# Pletacka_board.net
KiCad netlist of a schematic drawn in EAGLE
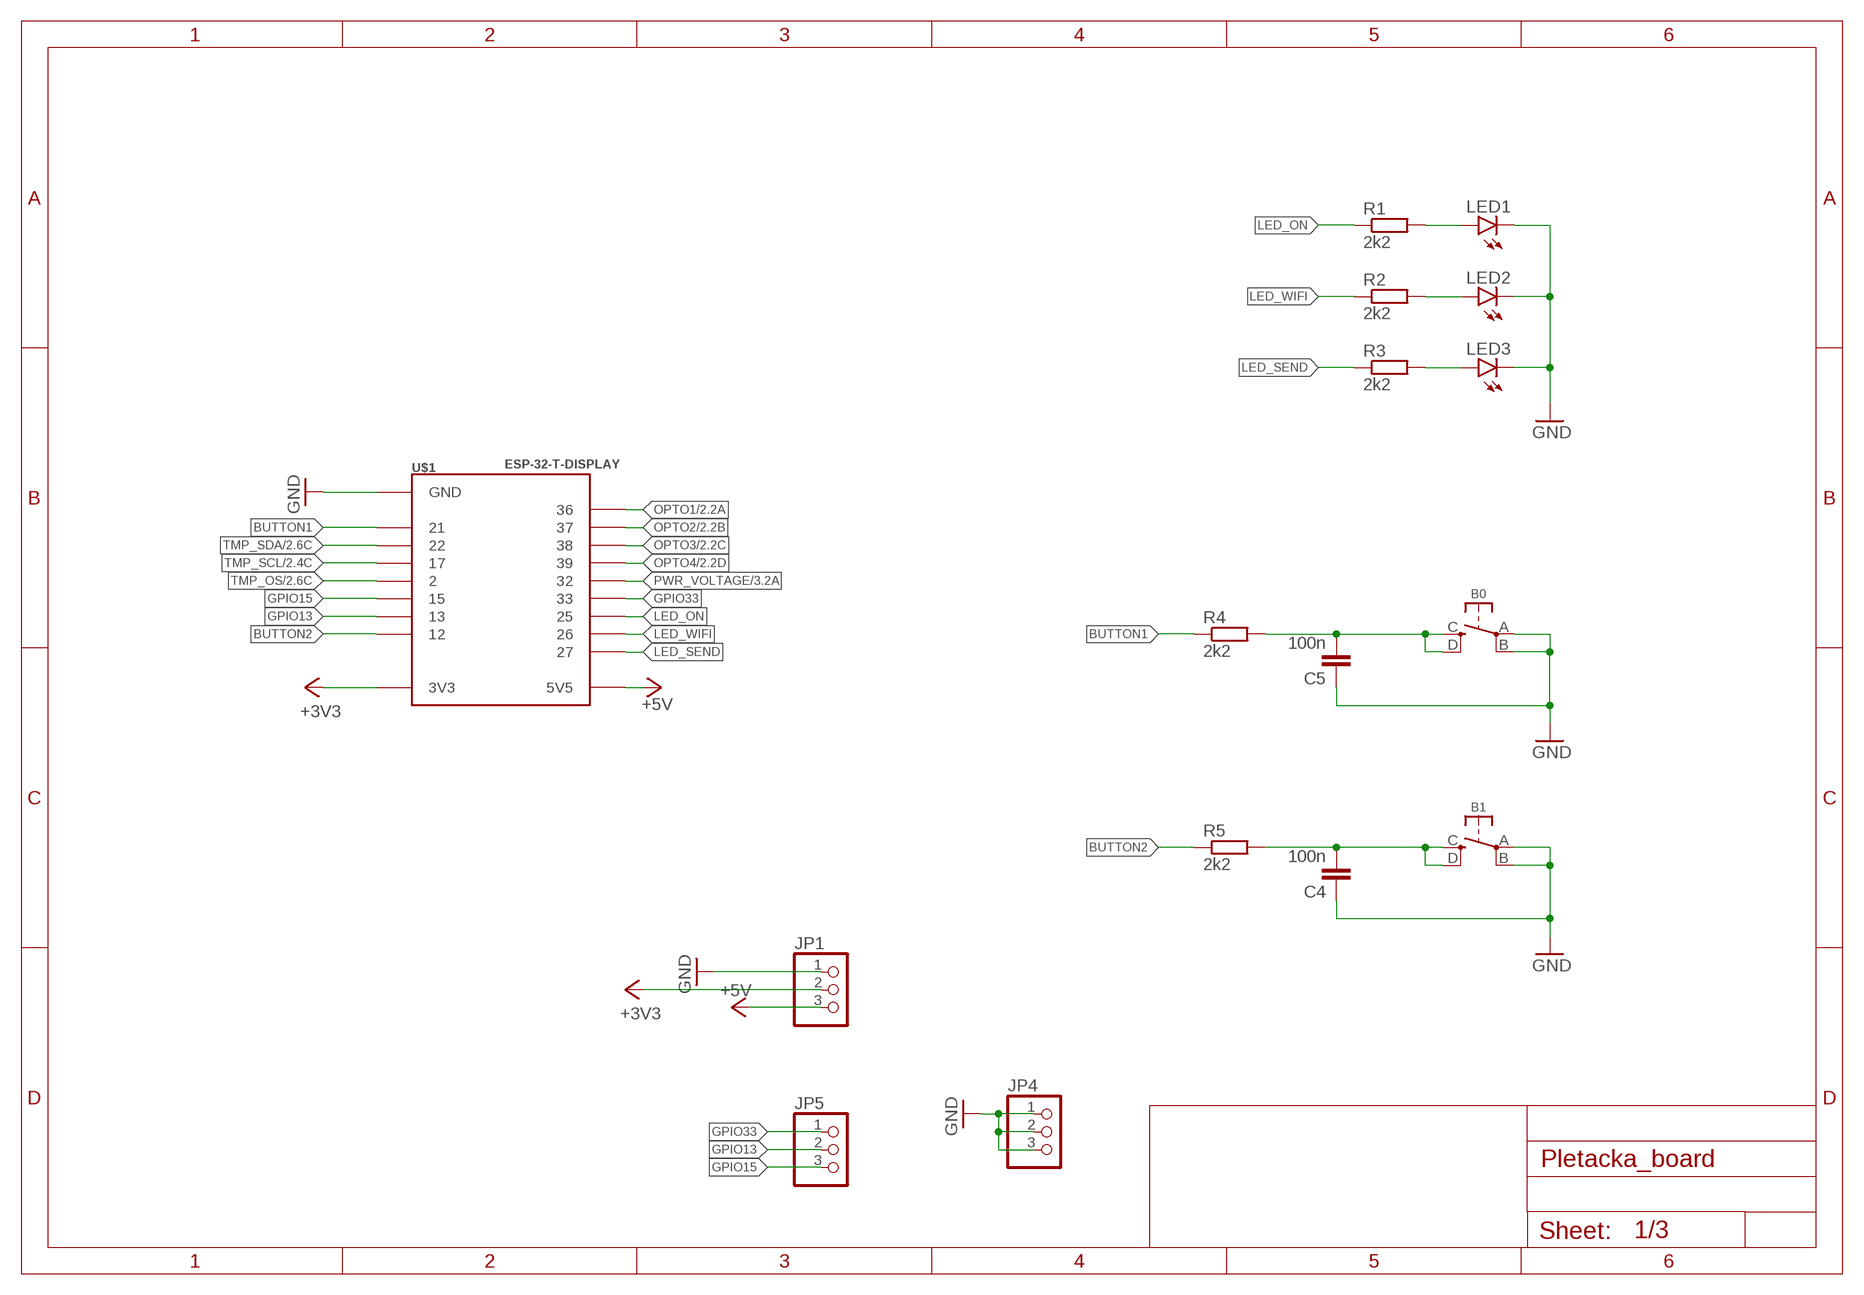
[diagram p0: schematic, sheet 1]
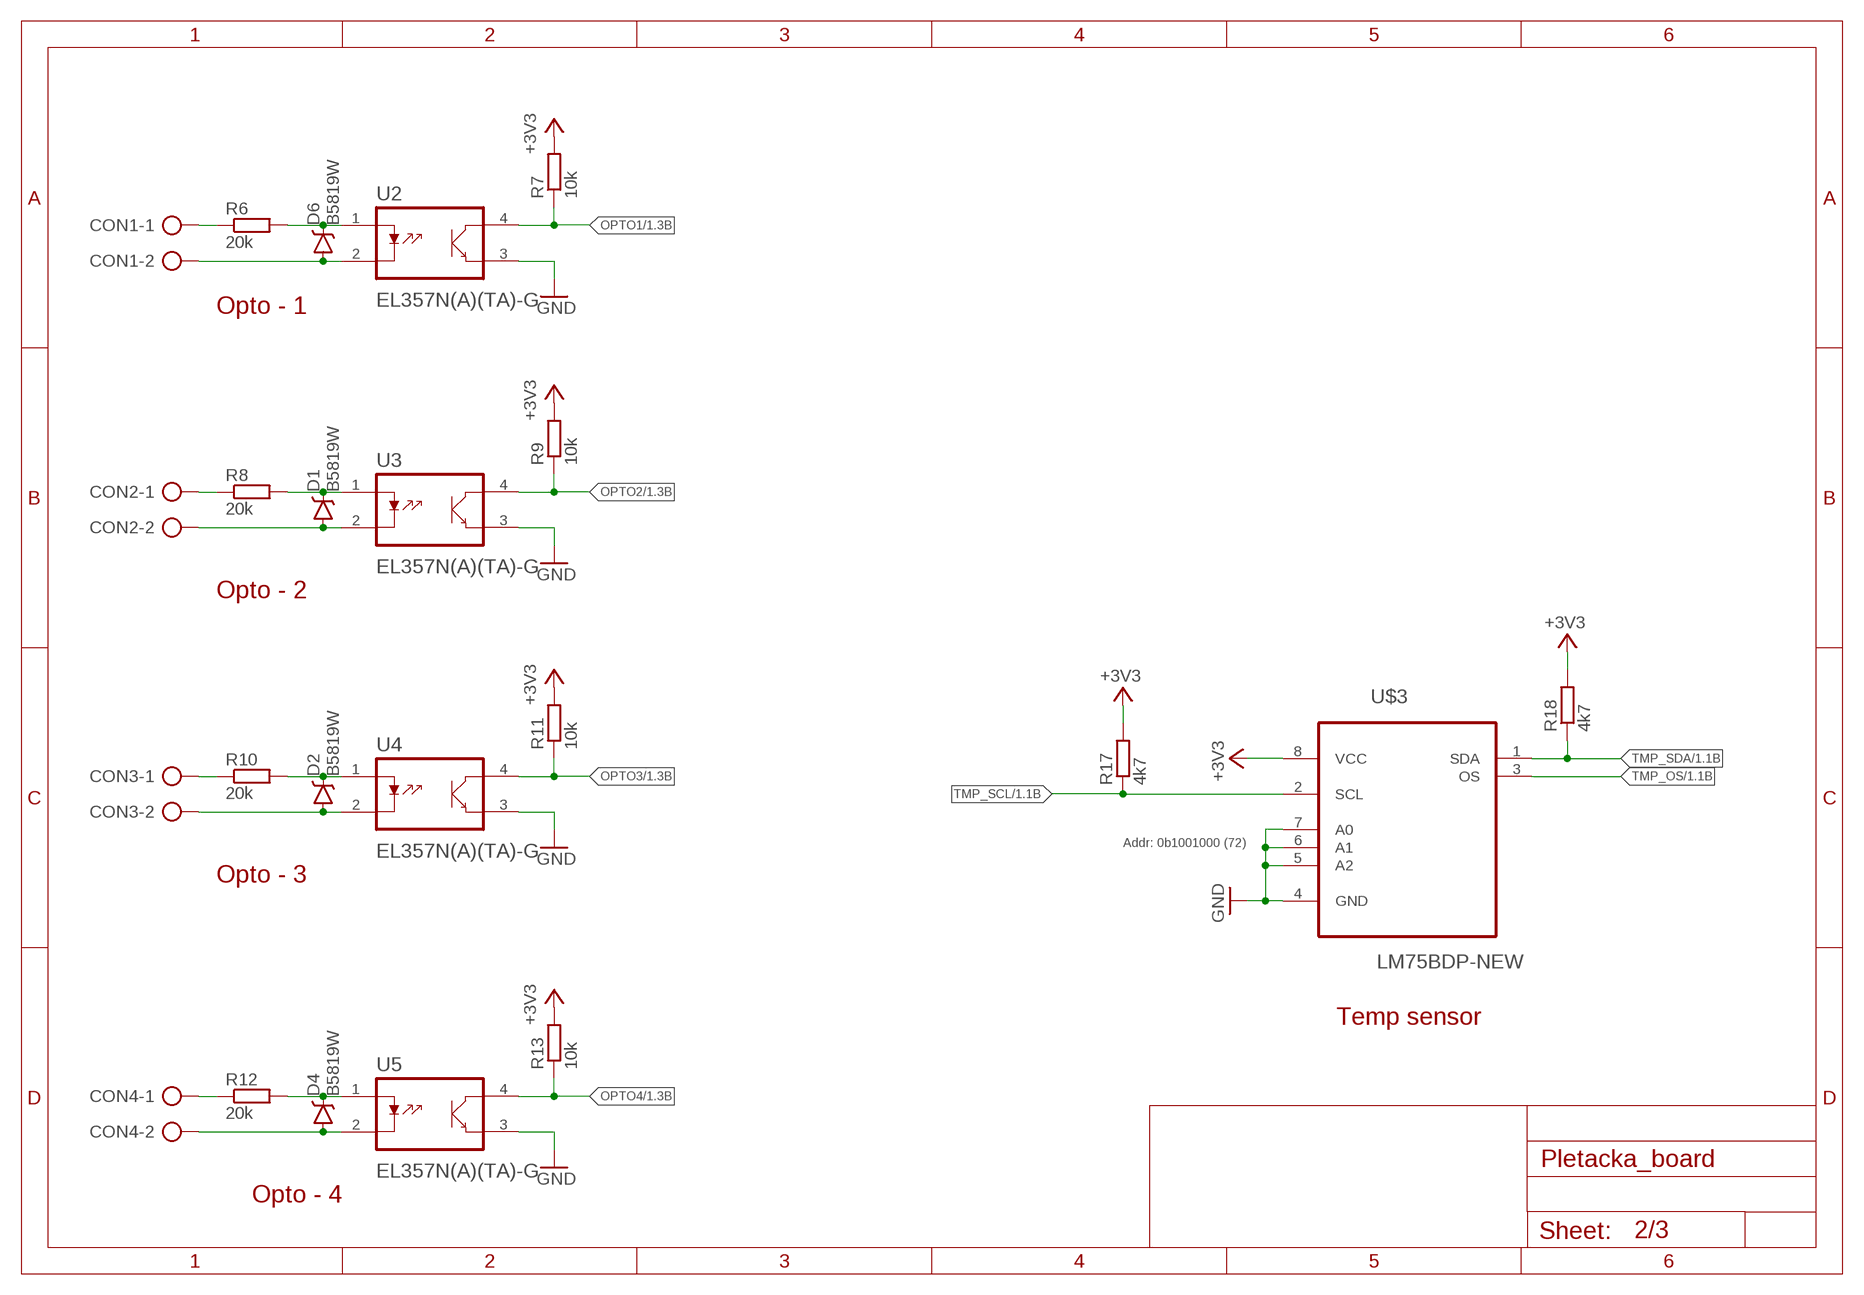
[diagram p1: schematic, sheet 2]
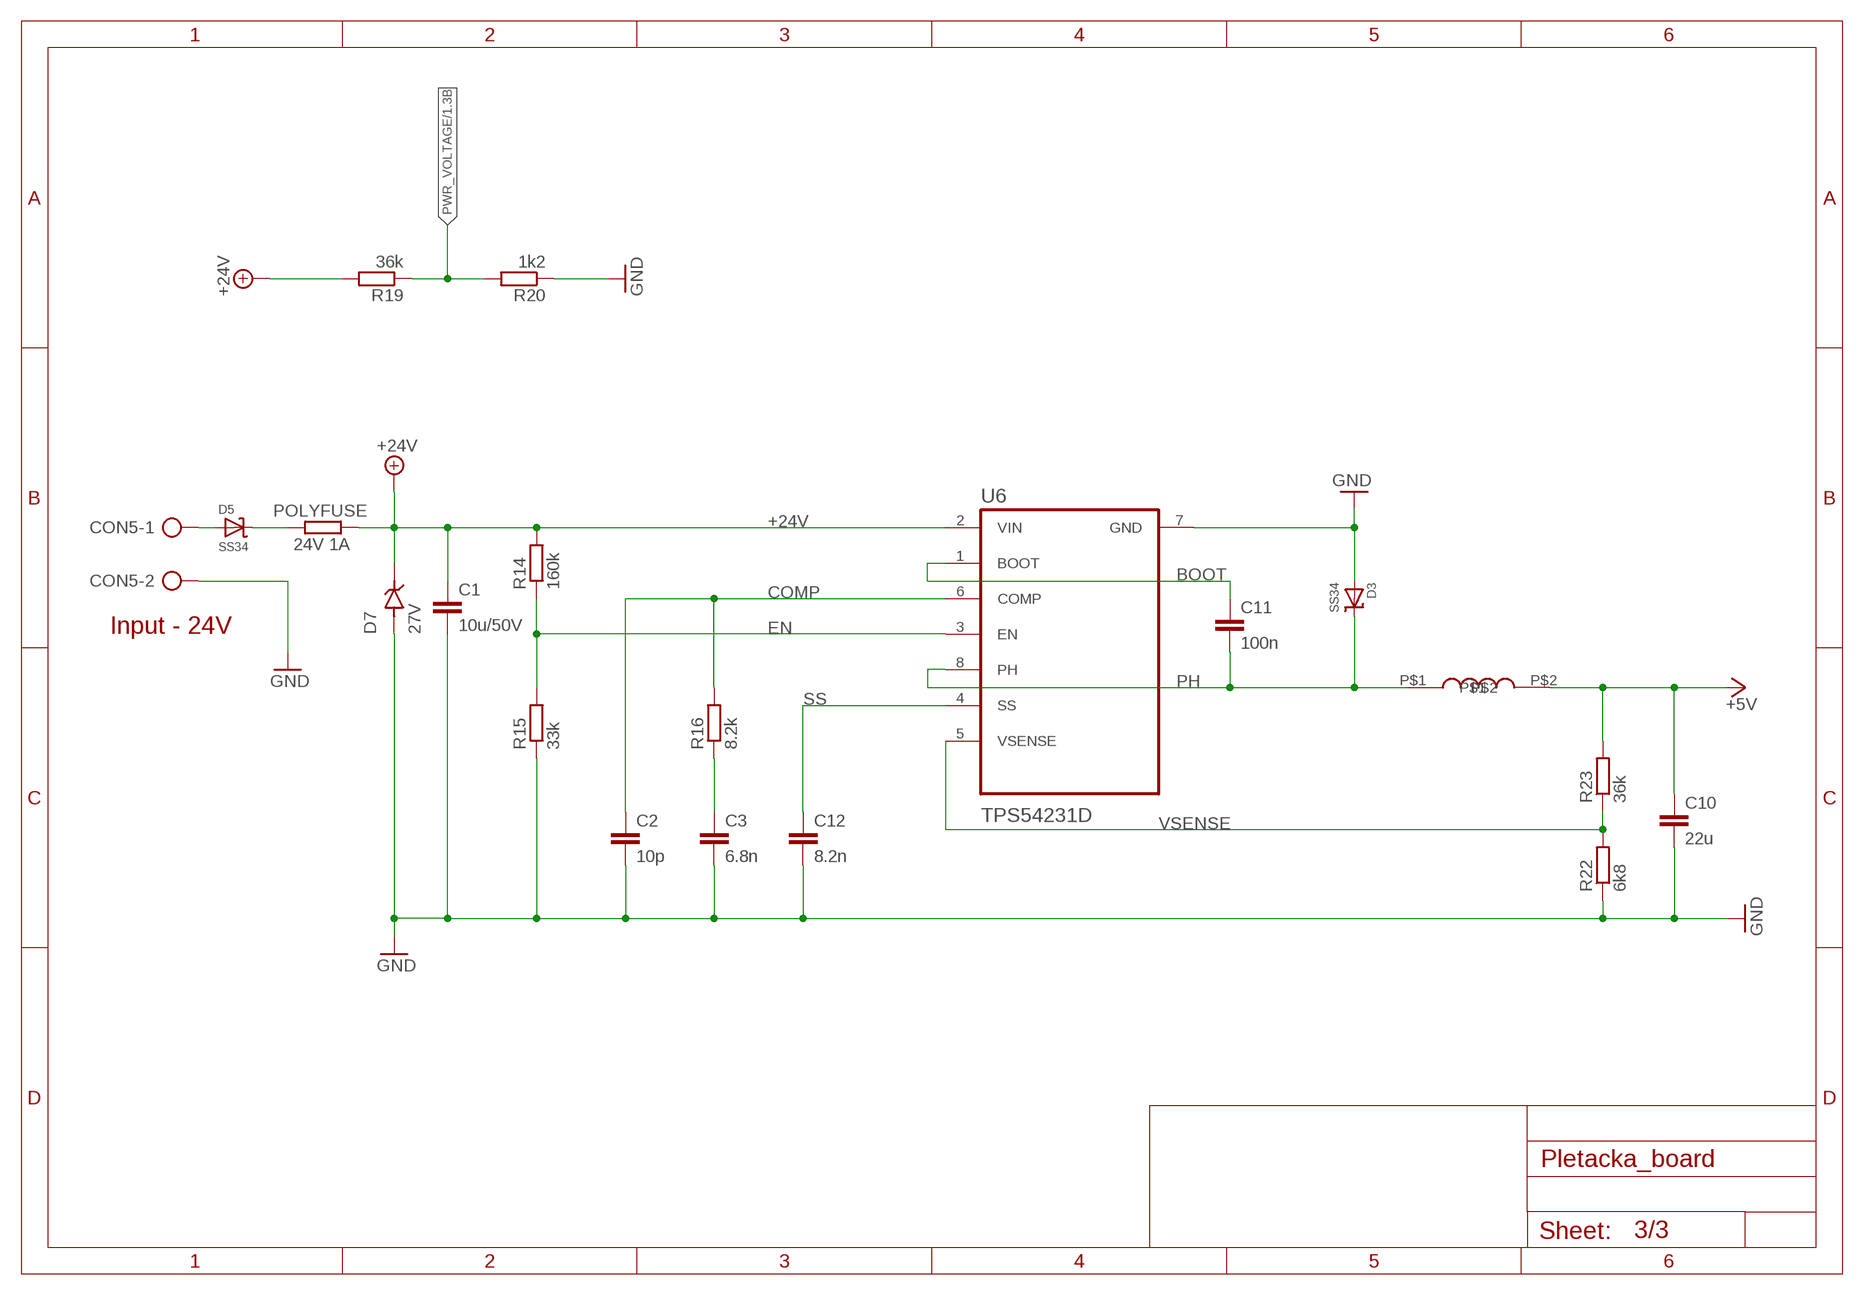
[diagram p2: schematic, sheet 3]

(export (version "E")
  (design (tool "Eeschema 10.0.6"))
  (components
    (comp (ref "C1")
      (value "10u/50V")
      (footprint "eagle-import:C1206")
      (libsource (lib "eagle-import") (part "C-EUC1206"))
    )
    (comp (ref "C2")
      (value "10p")
      (footprint "eagle-import:C0603")
      (libsource (lib "eagle-import") (part "C-EUC0603"))
    )
    (comp (ref "C3")
      (value "6.8n")
      (footprint "eagle-import:C0603")
      (libsource (lib "eagle-import") (part "C-EUC0603"))
    )
    (comp (ref "C10")
      (value "22u")
      (footprint "eagle-import:C0805")
      (libsource (lib "eagle-import") (part "C-EUC0805"))
    )
    (comp (ref "C11")
      (value "100n")
      (footprint "eagle-import:C0603")
      (libsource (lib "eagle-import") (part "C-EUC0603"))
    )
    (comp (ref "C12")
      (value "8.2n")
      (footprint "eagle-import:C0603")
      (libsource (lib "eagle-import") (part "C-EUC0603"))
    )
    (comp (ref "CON5")
      (value "AK500/2")
      (footprint "eagle-import:AK500_2")
      (libsource (lib "eagle-import") (part "AK500/2"))
    )
    (comp (ref "D3")
      (value "SS34")
      (footprint "eagle-import:SMA")
      (libsource (lib "eagle-import") (part "SHOTTKY-SMA"))
    )
    (comp (ref "D5")
      (value "SS34")
      (footprint "eagle-import:SMA")
      (libsource (lib "eagle-import") (part "SHOTTKY-SMA"))
    )
    (comp (ref "D7")
      (value "27V")
      (footprint "eagle-import:DIOM5436X247N")
      (fields (field (name "MF") "ON Semiconductor") (field (name "MP") "1SMB5935BT3G"))
      (libsource (lib "eagle-import") (part "1SMB5935BT3G"))
    )
    (comp (ref "POLYFUSE")
      (value "24V 1A")
      (footprint "eagle-import:R1206")
      (libsource (lib "eagle-import") (part "R-EU_R1206"))
    )
    (comp (ref "R14")
      (value "160k")
      (footprint "eagle-import:R0603")
      (libsource (lib "eagle-import") (part "R-EU_R0603"))
    )
    (comp (ref "R15")
      (value "33k")
      (footprint "eagle-import:R0603")
      (libsource (lib "eagle-import") (part "R-EU_R0603"))
    )
    (comp (ref "R16")
      (value "8.2k")
      (footprint "eagle-import:R0603")
      (libsource (lib "eagle-import") (part "R-EU_R0603"))
    )
    (comp (ref "R19")
      (value "36k")
      (footprint "eagle-import:R0603")
      (libsource (lib "eagle-import") (part "R-EU_R0603"))
    )
    (comp (ref "R20")
      (value "1k2")
      (footprint "eagle-import:R0603")
      (libsource (lib "eagle-import") (part "R-EU_R0603"))
    )
    (comp (ref "R22")
      (value "6k8")
      (footprint "eagle-import:R0603")
      (libsource (lib "eagle-import") (part "R-EU_R0603"))
    )
    (comp (ref "R23")
      (value "36k")
      (footprint "eagle-import:R0603")
      (libsource (lib "eagle-import") (part "R-EU_R0603"))
    )
    (comp (ref "U$2")
      (value "SWRB1204S")
      (footprint "eagle-import:SWRB1204S")
      (libsource (lib "eagle-import") (part "SWRB1204S"))
    )
    (comp (ref "U6")
      (value "TPS54231D")
      (footprint "eagle-import:SOIC127P599X175-8N")
      (description "3.5 to 28V Input, 2A, 570kHz Step-Down Converter with Eco-mode&trade, 8-SOIC -40 to 150")
      (fields (field (name "MF") "Texas Instruments"))
      (libsource (lib "eagle-import") (part "TPS54231D"))
    )
    (comp (ref "B0")
      (value "ENTER")
      (footprint "eagle-import:TS-1187A")
      (libsource (lib "eagle-import") (part "10-XX_SMD"))
    )
    (comp (ref "B1")
      (value "B1")
      (footprint "eagle-import:TS-1187A")
      (libsource (lib "eagle-import") (part "10-XX_SMD"))
    )
    (comp (ref "C4")
      (value "100n")
      (footprint "eagle-import:C0603")
      (libsource (lib "eagle-import") (part "C-EUC0603"))
    )
    (comp (ref "C5")
      (value "100n")
      (footprint "eagle-import:C0603")
      (libsource (lib "eagle-import") (part "C-EUC0603"))
    )
    (comp (ref "JP1")
      (value "PINHD-1X3")
      (footprint "eagle-import:1X03")
      (libsource (lib "eagle-import") (part "PINHD-1X3"))
    )
    (comp (ref "JP4")
      (value "PINHD-1X3")
      (footprint "eagle-import:1X03")
      (libsource (lib "eagle-import") (part "PINHD-1X3"))
    )
    (comp (ref "JP5")
      (value "PINHD-1X3")
      (footprint "eagle-import:1X03")
      (libsource (lib "eagle-import") (part "PINHD-1X3"))
    )
    (comp (ref "LED1")
      (value "LEDCHIPLED_0603")
      (footprint "eagle-import:CHIPLED_0603")
      (libsource (lib "eagle-import") (part "LEDCHIPLED_0603"))
    )
    (comp (ref "LED2")
      (value "LEDCHIPLED_0603")
      (footprint "eagle-import:CHIPLED_0603")
      (libsource (lib "eagle-import") (part "LEDCHIPLED_0603"))
    )
    (comp (ref "LED3")
      (value "LEDCHIPLED_0603")
      (footprint "eagle-import:CHIPLED_0603")
      (libsource (lib "eagle-import") (part "LEDCHIPLED_0603"))
    )
    (comp (ref "R1")
      (value "2k2")
      (footprint "eagle-import:R0603")
      (libsource (lib "eagle-import") (part "R-EU_R0603"))
    )
    (comp (ref "R2")
      (value "2k2")
      (footprint "eagle-import:R0603")
      (libsource (lib "eagle-import") (part "R-EU_R0603"))
    )
    (comp (ref "R3")
      (value "2k2")
      (footprint "eagle-import:R0603")
      (libsource (lib "eagle-import") (part "R-EU_R0603"))
    )
    (comp (ref "R4")
      (value "2k2")
      (footprint "eagle-import:R0603")
      (libsource (lib "eagle-import") (part "R-EU_R0603"))
    )
    (comp (ref "R5")
      (value "2k2")
      (footprint "eagle-import:R0603")
      (libsource (lib "eagle-import") (part "R-EU_R0603"))
    )
    (comp (ref "U$1")
      (value "ESP-32-T-DISPLAY")
      (footprint "eagle-import:ESP32-T-DISPLAY")
      (libsource (lib "eagle-import") (part "ESP-32-T-DISPLAY"))
    )
    (comp (ref "CON1")
      (value "AK500/2")
      (footprint "eagle-import:AK500_2")
      (libsource (lib "eagle-import") (part "AK500/2"))
    )
    (comp (ref "CON2")
      (value "AK500/2")
      (footprint "eagle-import:AK500_2")
      (libsource (lib "eagle-import") (part "AK500/2"))
    )
    (comp (ref "CON3")
      (value "AK500/2")
      (footprint "eagle-import:AK500_2")
      (libsource (lib "eagle-import") (part "AK500/2"))
    )
    (comp (ref "CON4")
      (value "AK500/2")
      (footprint "eagle-import:AK500_2")
      (libsource (lib "eagle-import") (part "AK500/2"))
    )
    (comp (ref "D1")
      (value "B5819W")
      (footprint "eagle-import:SOD-123")
      (fields (field (name "MF") "Taiwan Semiconductor"))
      (libsource (lib "eagle-import") (part "B5819W"))
    )
    (comp (ref "D2")
      (value "B5819W")
      (footprint "eagle-import:SOD-123")
      (fields (field (name "MF") "Taiwan Semiconductor"))
      (libsource (lib "eagle-import") (part "B5819W"))
    )
    (comp (ref "D4")
      (value "B5819W")
      (footprint "eagle-import:SOD-123")
      (fields (field (name "MF") "Taiwan Semiconductor"))
      (libsource (lib "eagle-import") (part "B5819W"))
    )
    (comp (ref "D6")
      (value "B5819W")
      (footprint "eagle-import:SOD-123")
      (fields (field (name "MF") "Taiwan Semiconductor"))
      (libsource (lib "eagle-import") (part "B5819W"))
    )
    (comp (ref "R6")
      (value "20k")
      (footprint "eagle-import:R0603")
      (libsource (lib "eagle-import") (part "R-EU_R0603"))
    )
    (comp (ref "R7")
      (value "10k")
      (footprint "eagle-import:R0603")
      (libsource (lib "eagle-import") (part "R-EU_R0603"))
    )
    (comp (ref "R8")
      (value "20k")
      (footprint "eagle-import:R0603")
      (libsource (lib "eagle-import") (part "R-EU_R0603"))
    )
    (comp (ref "R9")
      (value "10k")
      (footprint "eagle-import:R0603")
      (libsource (lib "eagle-import") (part "R-EU_R0603"))
    )
    (comp (ref "R10")
      (value "20k")
      (footprint "eagle-import:R0603")
      (libsource (lib "eagle-import") (part "R-EU_R0603"))
    )
    (comp (ref "R11")
      (value "10k")
      (footprint "eagle-import:R0603")
      (libsource (lib "eagle-import") (part "R-EU_R0603"))
    )
    (comp (ref "R12")
      (value "20k")
      (footprint "eagle-import:R0603")
      (libsource (lib "eagle-import") (part "R-EU_R0603"))
    )
    (comp (ref "R13")
      (value "10k")
      (footprint "eagle-import:R0603")
      (libsource (lib "eagle-import") (part "R-EU_R0603"))
    )
    (comp (ref "R17")
      (value "4k7")
      (footprint "eagle-import:R0603")
      (libsource (lib "eagle-import") (part "R-EU_R0603"))
    )
    (comp (ref "R18")
      (value "4k7")
      (footprint "eagle-import:R0603")
      (libsource (lib "eagle-import") (part "R-EU_R0603"))
    )
    (comp (ref "U$3")
      (value "LM75BDP-NEW")
      (footprint "eagle-import:SOT505-1")
      (libsource (lib "eagle-import") (part "LM75BDP-NEW"))
    )
    (comp (ref "U2")
      (value "EL357N(A)(TA)-G")
      (footprint "eagle-import:SOP254P700X200-4N")
      (fields (field (name "MF") "Everlight Electronics"))
      (libsource (lib "eagle-import") (part "EL357N(A)(TA)-G"))
    )
    (comp (ref "U3")
      (value "EL357N(A)(TA)-G")
      (footprint "eagle-import:SOP254P700X200-4N")
      (fields (field (name "MF") "Everlight Electronics"))
      (libsource (lib "eagle-import") (part "EL357N(A)(TA)-G"))
    )
    (comp (ref "U4")
      (value "EL357N(A)(TA)-G")
      (footprint "eagle-import:SOP254P700X200-4N")
      (fields (field (name "MF") "Everlight Electronics"))
      (libsource (lib "eagle-import") (part "EL357N(A)(TA)-G"))
    )
    (comp (ref "U5")
      (value "EL357N(A)(TA)-G")
      (footprint "eagle-import:SOP254P700X200-4N")
      (fields (field (name "MF") "Everlight Electronics"))
      (libsource (lib "eagle-import") (part "EL357N(A)(TA)-G"))
    )
  )
  (nets
    (net (code "1") (name "+3V3") (class "Default")
      (node (ref "JP1") (pin "2") (pinfunction "2_2") (pintype "passive"))
      (node (ref "R11") (pin "2") (pinfunction "2_2") (pintype "passive"))
      (node (ref "R13") (pin "2") (pinfunction "2_2") (pintype "passive"))
      (node (ref "R17") (pin "2") (pinfunction "2_2") (pintype "passive"))
      (node (ref "R18") (pin "2") (pinfunction "2_2") (pintype "passive"))
      (node (ref "R7") (pin "2") (pinfunction "2_2") (pintype "passive"))
      (node (ref "R9") (pin "2") (pinfunction "2_2") (pintype "passive"))
      (node (ref "U$1") (pin "3V3") (pinfunction "3V3_3V3") (pintype "bidirectional"))
      (node (ref "U$1") (pin "3V3-2") (pinfunction "3V3_3V3-2") (pintype "bidirectional"))
      (node (ref "U$3") (pin "8") (pinfunction "VCC_8") (pintype "power_in"))
    )
    (net (code "2") (name "+5V") (class "Default")
      (node (ref "C10") (pin "1") (pinfunction "1_1") (pintype "passive"))
      (node (ref "JP1") (pin "3") (pinfunction "3_3") (pintype "passive"))
      (node (ref "R23") (pin "2") (pinfunction "2_2") (pintype "passive"))
      (node (ref "U$1") (pin "5V") (pinfunction "5V5_5V") (pintype "bidirectional"))
      (node (ref "U$2") (pin "P$2") (pinfunction "P$2_P$2") (pintype "bidirectional"))
    )
    (net (code "3") (name "+24V") (class "Default")
      (node (ref "C1") (pin "1") (pinfunction "1_1") (pintype "passive"))
      (node (ref "D7") (pin "C") (pinfunction "K_C") (pintype "passive"))
      (node (ref "POLYFUSE") (pin "1") (pinfunction "1_1") (pintype "passive"))
      (node (ref "R14") (pin "2") (pinfunction "2_2") (pintype "passive"))
      (node (ref "R19") (pin "2") (pinfunction "2_2") (pintype "passive"))
      (node (ref "U6") (pin "2") (pinfunction "VIN_2") (pintype "input"))
    )
    (net (code "4") (name "BOOT") (class "Default")
      (node (ref "C11") (pin "1") (pinfunction "1_1") (pintype "passive"))
      (node (ref "U6") (pin "1") (pinfunction "BOOT_1") (pintype "bidirectional"))
    )
    (net (code "5") (name "BUTTON1") (class "Default")
      (node (ref "R4") (pin "1") (pinfunction "1_1") (pintype "passive"))
      (node (ref "U$1") (pin "21") (pinfunction "21_21") (pintype "bidirectional"))
    )
    (net (code "6") (name "BUTTON2") (class "Default")
      (node (ref "R5") (pin "1") (pinfunction "1_1") (pintype "passive"))
      (node (ref "U$1") (pin "12") (pinfunction "12_12") (pintype "bidirectional"))
    )
    (net (code "7") (name "COMP") (class "Default")
      (node (ref "C2") (pin "1") (pinfunction "1_1") (pintype "passive"))
      (node (ref "R16") (pin "2") (pinfunction "2_2") (pintype "passive"))
      (node (ref "U6") (pin "6") (pinfunction "COMP_6") (pintype "bidirectional"))
    )
    (net (code "8") (name "EN") (class "Default")
      (node (ref "R14") (pin "1") (pinfunction "1_1") (pintype "passive"))
      (node (ref "R15") (pin "2") (pinfunction "2_2") (pintype "passive"))
      (node (ref "U6") (pin "3") (pinfunction "EN_3") (pintype "bidirectional"))
    )
    (net (code "9") (name "GND") (class "Default")
      (node (ref "B0") (pin "A") (pinfunction "P_A") (pintype "passive"))
      (node (ref "B0") (pin "B") (pinfunction "P1_B") (pintype "passive"))
      (node (ref "B1") (pin "A") (pinfunction "P_A") (pintype "passive"))
      (node (ref "B1") (pin "B") (pinfunction "P1_B") (pintype "passive"))
      (node (ref "C1") (pin "2") (pinfunction "2_2") (pintype "passive"))
      (node (ref "C10") (pin "2") (pinfunction "2_2") (pintype "passive"))
      (node (ref "C12") (pin "2") (pinfunction "2_2") (pintype "passive"))
      (node (ref "C2") (pin "2") (pinfunction "2_2") (pintype "passive"))
      (node (ref "C3") (pin "2") (pinfunction "2_2") (pintype "passive"))
      (node (ref "C4") (pin "1") (pinfunction "1_1") (pintype "passive"))
      (node (ref "C5") (pin "1") (pinfunction "1_1") (pintype "passive"))
      (node (ref "CON5") (pin "2") (pinfunction "KL_2") (pintype "passive"))
      (node (ref "D3") (pin "A") (pinfunction "A_A") (pintype "passive"))
      (node (ref "D7") (pin "A") (pinfunction "A_A") (pintype "passive"))
      (node (ref "JP1") (pin "1") (pinfunction "1_1") (pintype "passive"))
      (node (ref "JP4") (pin "1") (pinfunction "1_1") (pintype "passive"))
      (node (ref "JP4") (pin "2") (pinfunction "2_2") (pintype "passive"))
      (node (ref "JP4") (pin "3") (pinfunction "3_3") (pintype "passive"))
      (node (ref "LED1") (pin "C") (pinfunction "C_C") (pintype "passive"))
      (node (ref "LED2") (pin "C") (pinfunction "C_C") (pintype "passive"))
      (node (ref "LED3") (pin "C") (pinfunction "C_C") (pintype "passive"))
      (node (ref "R15") (pin "1") (pinfunction "1_1") (pintype "passive"))
      (node (ref "R20") (pin "1") (pinfunction "1_1") (pintype "passive"))
      (node (ref "R22") (pin "1") (pinfunction "1_1") (pintype "passive"))
      (node (ref "U$1") (pin "G-1") (pinfunction "GND_G-1") (pintype "bidirectional"))
      (node (ref "U$1") (pin "G-2") (pinfunction "GND_G-2") (pintype "bidirectional"))
      (node (ref "U$1") (pin "G-3") (pinfunction "GND_G-3") (pintype "bidirectional"))
      (node (ref "U$1") (pin "G-4") (pinfunction "GND_G-4") (pintype "bidirectional"))
      (node (ref "U$1") (pin "G-5") (pinfunction "GND_G-5") (pintype "bidirectional"))
      (node (ref "U$3") (pin "4") (pinfunction "GND_4") (pintype "passive"))
      (node (ref "U$3") (pin "5") (pinfunction "A2_5") (pintype "input"))
      (node (ref "U$3") (pin "6") (pinfunction "A1_6") (pintype "input"))
      (node (ref "U$3") (pin "7") (pinfunction "A0_7") (pintype "input"))
      (node (ref "U2") (pin "3") (pinfunction "E_3") (pintype "passive"))
      (node (ref "U3") (pin "3") (pinfunction "E_3") (pintype "passive"))
      (node (ref "U4") (pin "3") (pinfunction "E_3") (pintype "passive"))
      (node (ref "U5") (pin "3") (pinfunction "E_3") (pintype "passive"))
      (node (ref "U6") (pin "7") (pinfunction "GND_7") (pintype "power_in"))
    )
    (net (code "10") (name "GPIO13") (class "Default")
      (node (ref "JP5") (pin "2") (pinfunction "2_2") (pintype "passive"))
      (node (ref "U$1") (pin "13") (pinfunction "13_13") (pintype "bidirectional"))
    )
    (net (code "11") (name "GPIO15") (class "Default")
      (node (ref "JP5") (pin "3") (pinfunction "3_3") (pintype "passive"))
      (node (ref "U$1") (pin "15") (pinfunction "15_15") (pintype "bidirectional"))
    )
    (net (code "12") (name "GPIO33") (class "Default")
      (node (ref "JP5") (pin "1") (pinfunction "1_1") (pintype "passive"))
      (node (ref "U$1") (pin "33") (pinfunction "33_33") (pintype "bidirectional"))
    )
    (net (code "13") (name "LED_ON") (class "Default")
      (node (ref "R1") (pin "1") (pinfunction "1_1") (pintype "passive"))
      (node (ref "U$1") (pin "25") (pinfunction "25_25") (pintype "bidirectional"))
    )
    (net (code "14") (name "LED_SEND") (class "Default")
      (node (ref "R3") (pin "1") (pinfunction "1_1") (pintype "passive"))
      (node (ref "U$1") (pin "27") (pinfunction "27_27") (pintype "bidirectional"))
    )
    (net (code "15") (name "LED_WIFI") (class "Default")
      (node (ref "R2") (pin "1") (pinfunction "1_1") (pintype "passive"))
      (node (ref "U$1") (pin "26") (pinfunction "26_26") (pintype "bidirectional"))
    )
    (net (code "16") (name "Net-(B0-S)") (class "Default")
      (node (ref "B0") (pin "C") (pinfunction "S_C") (pintype "passive"))
      (node (ref "B0") (pin "D") (pinfunction "S1_D") (pintype "passive"))
      (node (ref "C5") (pin "2") (pinfunction "2_2") (pintype "passive"))
      (node (ref "R4") (pin "2") (pinfunction "2_2") (pintype "passive"))
    )
    (net (code "17") (name "Net-(B1-S)") (class "Default")
      (node (ref "B1") (pin "C") (pinfunction "S_C") (pintype "passive"))
      (node (ref "B1") (pin "D") (pinfunction "S1_D") (pintype "passive"))
      (node (ref "C4") (pin "2") (pinfunction "2_2") (pintype "passive"))
      (node (ref "R5") (pin "2") (pinfunction "2_2") (pintype "passive"))
    )
    (net (code "18") (name "Net-(C3-Pad1)") (class "Default")
      (node (ref "C3") (pin "1") (pinfunction "1_1") (pintype "passive"))
      (node (ref "R16") (pin "1") (pinfunction "1_1") (pintype "passive"))
    )
    (net (code "19") (name "Net-(CON1A-KL)") (class "Default")
      (node (ref "CON1") (pin "1") (pinfunction "KL_1") (pintype "passive"))
      (node (ref "R6") (pin "1") (pinfunction "1_1") (pintype "passive"))
    )
    (net (code "20") (name "Net-(CON1B-KL)") (class "Default")
      (node (ref "CON1") (pin "2") (pinfunction "KL_2") (pintype "passive"))
      (node (ref "D6") (pin "A") (pinfunction "A_A") (pintype "passive"))
      (node (ref "U2") (pin "2") (pinfunction "K_2") (pintype "passive"))
    )
    (net (code "21") (name "Net-(CON2A-KL)") (class "Default")
      (node (ref "CON2") (pin "1") (pinfunction "KL_1") (pintype "passive"))
      (node (ref "R8") (pin "1") (pinfunction "1_1") (pintype "passive"))
    )
    (net (code "22") (name "Net-(CON2B-KL)") (class "Default")
      (node (ref "CON2") (pin "2") (pinfunction "KL_2") (pintype "passive"))
      (node (ref "D1") (pin "A") (pinfunction "A_A") (pintype "passive"))
      (node (ref "U3") (pin "2") (pinfunction "K_2") (pintype "passive"))
    )
    (net (code "23") (name "Net-(CON3A-KL)") (class "Default")
      (node (ref "CON3") (pin "1") (pinfunction "KL_1") (pintype "passive"))
      (node (ref "R10") (pin "1") (pinfunction "1_1") (pintype "passive"))
    )
    (net (code "24") (name "Net-(CON3B-KL)") (class "Default")
      (node (ref "CON3") (pin "2") (pinfunction "KL_2") (pintype "passive"))
      (node (ref "D2") (pin "A") (pinfunction "A_A") (pintype "passive"))
      (node (ref "U4") (pin "2") (pinfunction "K_2") (pintype "passive"))
    )
    (net (code "25") (name "Net-(CON4A-KL)") (class "Default")
      (node (ref "CON4") (pin "1") (pinfunction "KL_1") (pintype "passive"))
      (node (ref "R12") (pin "1") (pinfunction "1_1") (pintype "passive"))
    )
    (net (code "26") (name "Net-(CON4B-KL)") (class "Default")
      (node (ref "CON4") (pin "2") (pinfunction "KL_2") (pintype "passive"))
      (node (ref "D4") (pin "A") (pinfunction "A_A") (pintype "passive"))
      (node (ref "U5") (pin "2") (pinfunction "K_2") (pintype "passive"))
    )
    (net (code "27") (name "Net-(CON5A-KL)") (class "Default")
      (node (ref "CON5") (pin "1") (pinfunction "KL_1") (pintype "passive"))
      (node (ref "D5") (pin "A") (pinfunction "A_A") (pintype "passive"))
    )
    (net (code "28") (name "Net-(D5-PadC)") (class "Default")
      (node (ref "D5") (pin "C") (pinfunction "C_C") (pintype "passive"))
      (node (ref "POLYFUSE") (pin "2") (pinfunction "2_2") (pintype "passive"))
    )
    (net (code "29") (name "Net-(LED1-PadA)") (class "Default")
      (node (ref "LED1") (pin "A") (pinfunction "A_A") (pintype "passive"))
      (node (ref "R1") (pin "2") (pinfunction "2_2") (pintype "passive"))
    )
    (net (code "30") (name "Net-(LED2-PadA)") (class "Default")
      (node (ref "LED2") (pin "A") (pinfunction "A_A") (pintype "passive"))
      (node (ref "R2") (pin "2") (pinfunction "2_2") (pintype "passive"))
    )
    (net (code "31") (name "Net-(LED3-PadA)") (class "Default")
      (node (ref "LED3") (pin "A") (pinfunction "A_A") (pintype "passive"))
      (node (ref "R3") (pin "2") (pinfunction "2_2") (pintype "passive"))
    )
    (net (code "32") (name "Net-(U2-A)") (class "Default")
      (node (ref "D6") (pin "C") (pinfunction "C_C") (pintype "passive"))
      (node (ref "R6") (pin "2") (pinfunction "2_2") (pintype "passive"))
      (node (ref "U2") (pin "1") (pinfunction "A_1") (pintype "passive"))
    )
    (net (code "33") (name "Net-(U3-A)") (class "Default")
      (node (ref "D1") (pin "C") (pinfunction "C_C") (pintype "passive"))
      (node (ref "R8") (pin "2") (pinfunction "2_2") (pintype "passive"))
      (node (ref "U3") (pin "1") (pinfunction "A_1") (pintype "passive"))
    )
    (net (code "34") (name "Net-(U4-A)") (class "Default")
      (node (ref "D2") (pin "C") (pinfunction "C_C") (pintype "passive"))
      (node (ref "R10") (pin "2") (pinfunction "2_2") (pintype "passive"))
      (node (ref "U4") (pin "1") (pinfunction "A_1") (pintype "passive"))
    )
    (net (code "35") (name "Net-(U5-A)") (class "Default")
      (node (ref "D4") (pin "C") (pinfunction "C_C") (pintype "passive"))
      (node (ref "R12") (pin "2") (pinfunction "2_2") (pintype "passive"))
      (node (ref "U5") (pin "1") (pinfunction "A_1") (pintype "passive"))
    )
    (net (code "36") (name "OPTO1") (class "Default")
      (node (ref "R7") (pin "1") (pinfunction "1_1") (pintype "passive"))
      (node (ref "U$1") (pin "36") (pinfunction "36_36") (pintype "bidirectional"))
      (node (ref "U2") (pin "4") (pinfunction "C_4") (pintype "passive"))
    )
    (net (code "37") (name "OPTO2") (class "Default")
      (node (ref "R9") (pin "1") (pinfunction "1_1") (pintype "passive"))
      (node (ref "U$1") (pin "37") (pinfunction "37_37") (pintype "bidirectional"))
      (node (ref "U3") (pin "4") (pinfunction "C_4") (pintype "passive"))
    )
    (net (code "38") (name "OPTO3") (class "Default")
      (node (ref "R11") (pin "1") (pinfunction "1_1") (pintype "passive"))
      (node (ref "U$1") (pin "38") (pinfunction "38_38") (pintype "bidirectional"))
      (node (ref "U4") (pin "4") (pinfunction "C_4") (pintype "passive"))
    )
    (net (code "39") (name "OPTO4") (class "Default")
      (node (ref "R13") (pin "1") (pinfunction "1_1") (pintype "passive"))
      (node (ref "U$1") (pin "39") (pinfunction "39_39") (pintype "bidirectional"))
      (node (ref "U5") (pin "4") (pinfunction "C_4") (pintype "passive"))
    )
    (net (code "40") (name "PH") (class "Default")
      (node (ref "C11") (pin "2") (pinfunction "2_2") (pintype "passive"))
      (node (ref "D3") (pin "C") (pinfunction "C_C") (pintype "passive"))
      (node (ref "U$2") (pin "P$1") (pinfunction "P$1_P$1") (pintype "bidirectional"))
      (node (ref "U6") (pin "8") (pinfunction "PH_8") (pintype "bidirectional"))
    )
    (net (code "41") (name "PWR_VOLTAGE") (class "Default")
      (node (ref "R19") (pin "1") (pinfunction "1_1") (pintype "passive"))
      (node (ref "R20") (pin "2") (pinfunction "2_2") (pintype "passive"))
      (node (ref "U$1") (pin "32") (pinfunction "32_32") (pintype "bidirectional"))
    )
    (net (code "42") (name "SS") (class "Default")
      (node (ref "C12") (pin "1") (pinfunction "1_1") (pintype "passive"))
      (node (ref "U6") (pin "4") (pinfunction "SS_4") (pintype "bidirectional"))
    )
    (net (code "43") (name "TMP_OS") (class "Default")
      (node (ref "U$1") (pin "2") (pinfunction "2_2") (pintype "bidirectional"))
      (node (ref "U$3") (pin "3") (pinfunction "OS_3") (pintype "output"))
    )
    (net (code "44") (name "TMP_SCL") (class "Default")
      (node (ref "R17") (pin "1") (pinfunction "1_1") (pintype "passive"))
      (node (ref "U$1") (pin "17") (pinfunction "17_17") (pintype "bidirectional"))
      (node (ref "U$3") (pin "2") (pinfunction "SCL_2") (pintype "input"))
    )
    (net (code "45") (name "TMP_SDA") (class "Default")
      (node (ref "R18") (pin "1") (pinfunction "1_1") (pintype "passive"))
      (node (ref "U$1") (pin "22") (pinfunction "22_22") (pintype "bidirectional"))
      (node (ref "U$3") (pin "1") (pinfunction "SDA_1") (pintype "bidirectional"))
    )
    (net (code "46") (name "VSENSE") (class "Default")
      (node (ref "R22") (pin "2") (pinfunction "2_2") (pintype "passive"))
      (node (ref "R23") (pin "1") (pinfunction "1_1") (pintype "passive"))
      (node (ref "U6") (pin "5") (pinfunction "VSENSE_5") (pintype "bidirectional"))
    )
  )
)
